# P2-sematik.net
KiCad netlist of a schematic drawn in Altium Designer
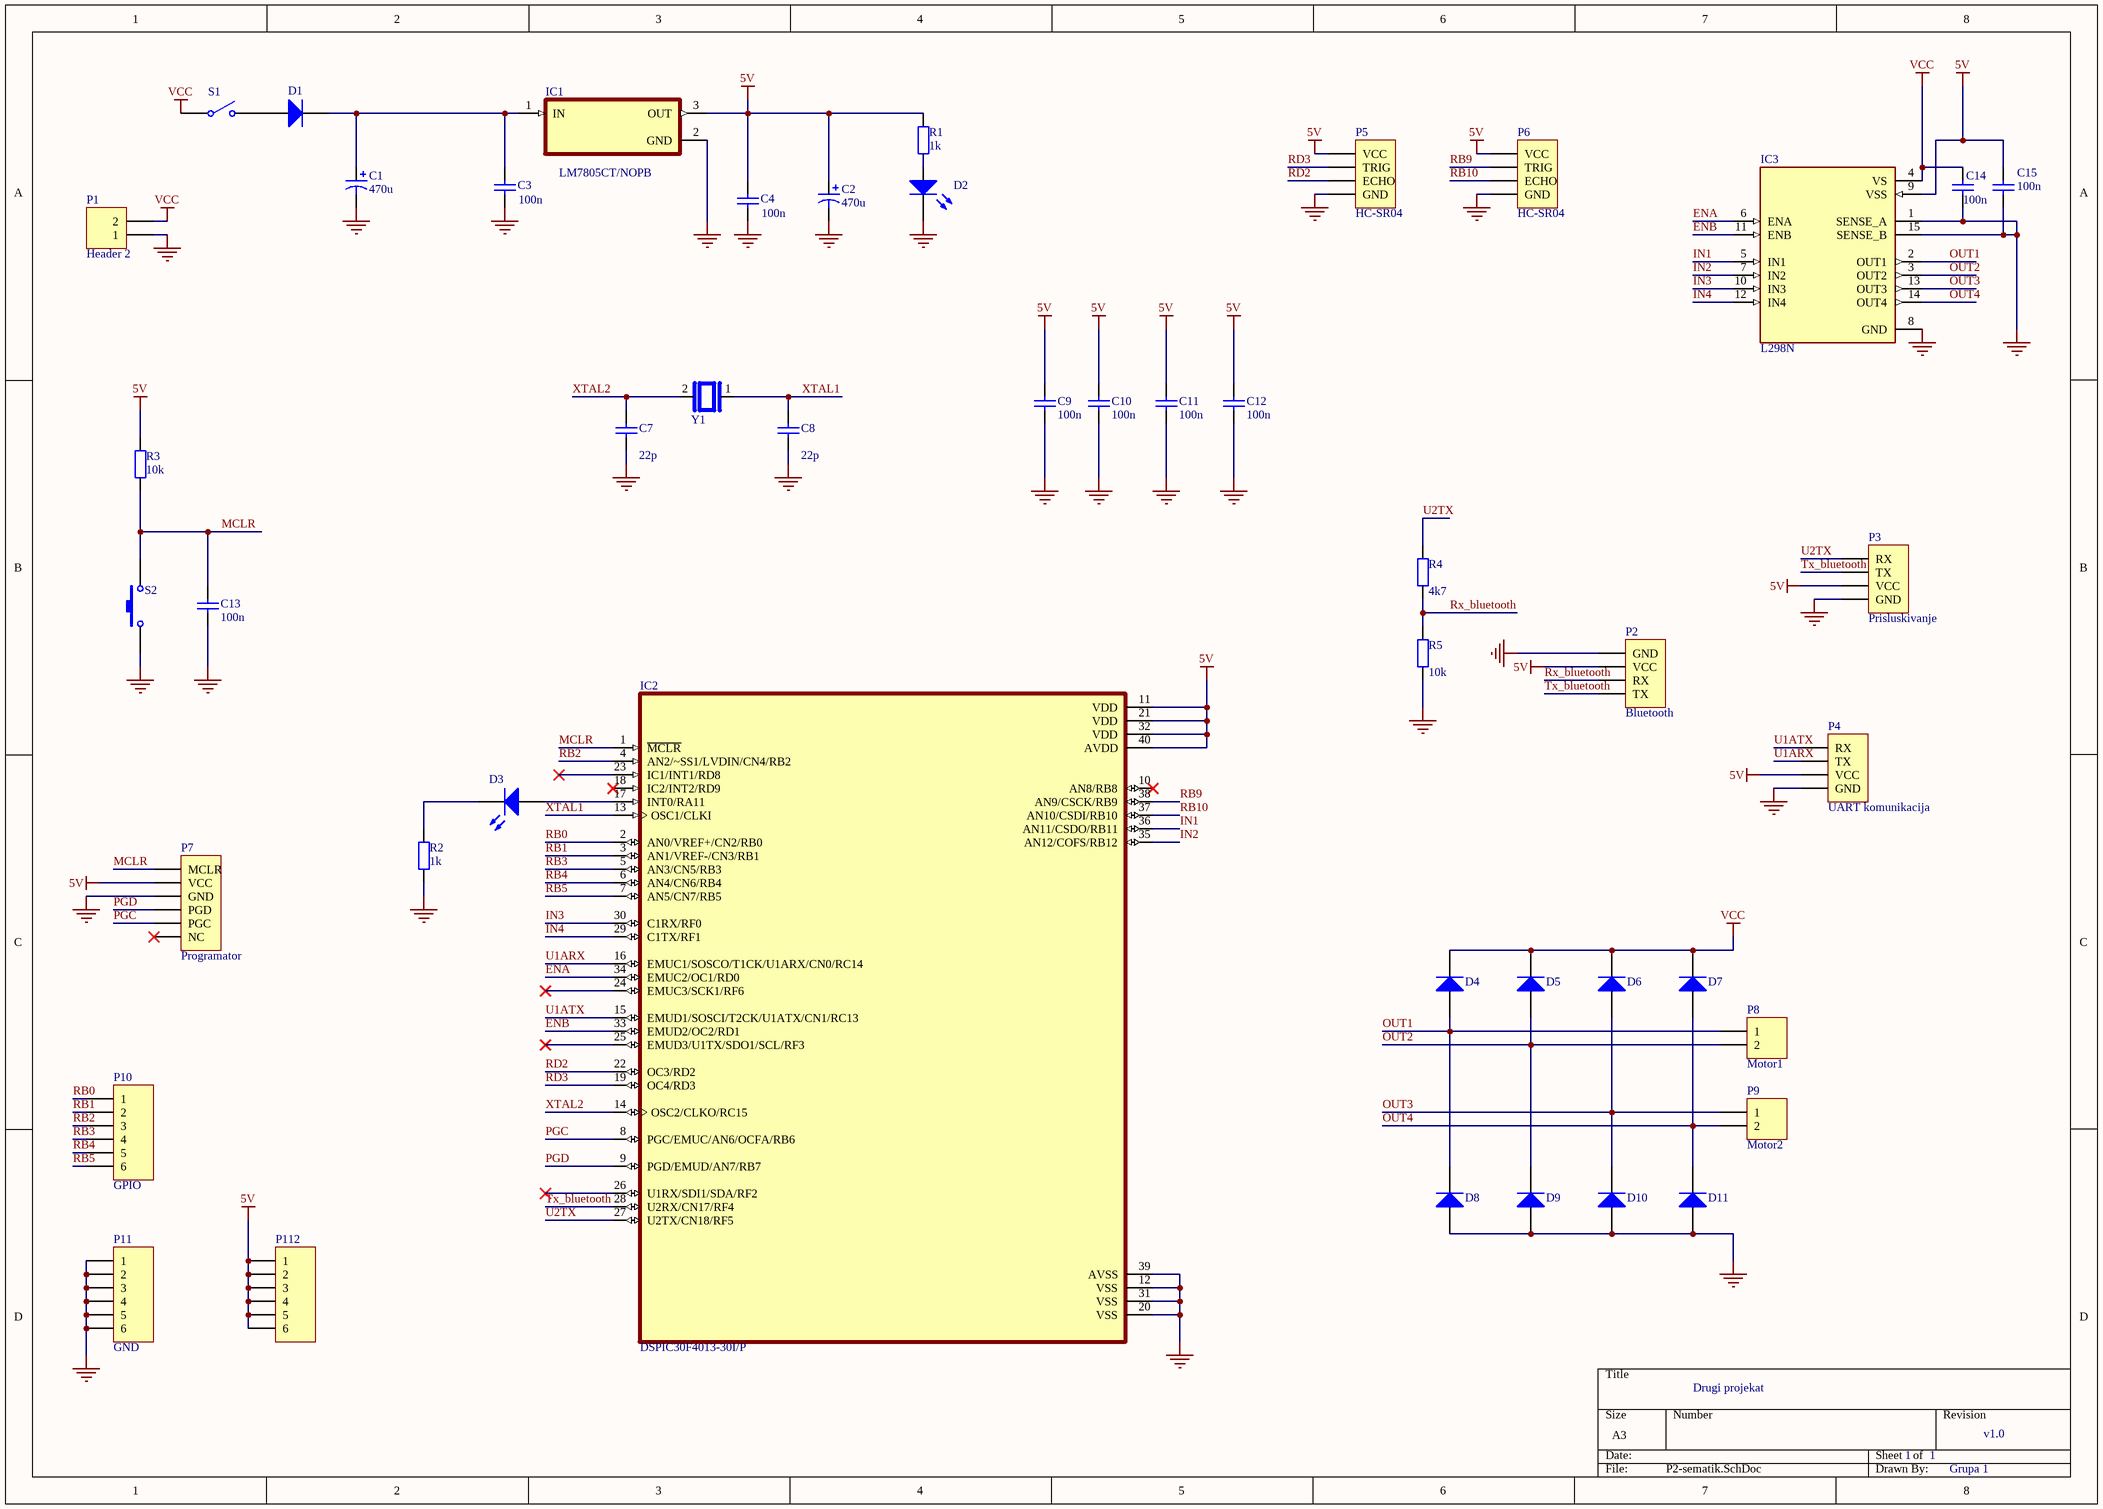
[diagram p0: P2-sematik.SchDoc]

(export (version "E")
  (design (tool "Eeschema 10.0.6"))
  (components
    (comp (ref "C1")
      (value "470u")
      (footprint "elektrolitski kondenzator")
      (description "Polarized Capacitor (Radial)")
      (fields (field (name "Comment") "Cap Pol1") (field (name "PUBLISHER") "Altium Limited"))
      (libsource (lib "Miscellaneous Devices") (part "Cap Pol1"))
    )
    (comp (ref "C2")
      (value "470u")
      (footprint "elektrolitski kondenzator")
      (description "Polarized Capacitor (Radial)")
      (fields (field (name "Comment") "Cap Pol1") (field (name "PUBLISHER") "Altium Limited"))
      (libsource (lib "Miscellaneous Devices") (part "Cap Pol1"))
    )
    (comp (ref "C3")
      (value "100n")
      (footprint "RAD-0.1")
      (description "Capacitor")
      (fields (field (name "Comment") "Cap") (field (name "PUBLISHER") "Altium Limited"))
      (libsource (lib "Miscellaneous Devices") (part "Cap"))
    )
    (comp (ref "C4")
      (value "100n")
      (footprint "RAD-0.1")
      (description "Capacitor")
      (fields (field (name "Comment") "Cap") (field (name "PUBLISHER") "Altium Limited"))
      (libsource (lib "Miscellaneous Devices") (part "Cap"))
    )
    (comp (ref "C7")
      (value "22p")
      (footprint "RAD-0.1")
      (description "Capacitor")
      (fields (field (name "Comment") "Cap") (field (name "PUBLISHER") "Altium Limited"))
      (libsource (lib "Miscellaneous Devices") (part "Cap"))
    )
    (comp (ref "C8")
      (value "22p")
      (footprint "RAD-0.1")
      (description "Capacitor")
      (fields (field (name "Comment") "Cap") (field (name "PUBLISHER") "Altium Limited"))
      (libsource (lib "Miscellaneous Devices") (part "Cap"))
    )
    (comp (ref "C9")
      (value "100n")
      (footprint "RAD-0.1")
      (description "Capacitor")
      (fields (field (name "Comment") "Cap") (field (name "PUBLISHER") "Altium Limited"))
      (libsource (lib "Miscellaneous Devices") (part "Cap"))
    )
    (comp (ref "C10")
      (value "100n")
      (footprint "RAD-0.1")
      (description "Capacitor")
      (fields (field (name "Comment") "Cap") (field (name "PUBLISHER") "Altium Limited"))
      (libsource (lib "Miscellaneous Devices") (part "Cap"))
    )
    (comp (ref "C11")
      (value "100n")
      (footprint "RAD-0.1")
      (description "Capacitor")
      (fields (field (name "Comment") "Cap") (field (name "PUBLISHER") "Altium Limited"))
      (libsource (lib "Miscellaneous Devices") (part "Cap"))
    )
    (comp (ref "C12")
      (value "100n")
      (footprint "RAD-0.1")
      (description "Capacitor")
      (fields (field (name "Comment") "Cap") (field (name "PUBLISHER") "Altium Limited"))
      (libsource (lib "Miscellaneous Devices") (part "Cap"))
    )
    (comp (ref "C13")
      (value "100n")
      (footprint "RAD-0.1")
      (description "Capacitor")
      (fields (field (name "Comment") "Cap") (field (name "PUBLISHER") "Altium Limited"))
      (libsource (lib "Miscellaneous Devices") (part "Cap"))
    )
    (comp (ref "C14")
      (value "100n")
      (footprint "RAD-0.1")
      (description "Capacitor")
      (fields (field (name "Comment") "Cap") (field (name "PUBLISHER") "Altium Limited"))
      (libsource (lib "Miscellaneous Devices") (part "Cap"))
    )
    (comp (ref "C15")
      (value "100n")
      (footprint "RAD-0.1")
      (description "Capacitor")
      (fields (field (name "Comment") "Cap") (field (name "PUBLISHER") "Altium Limited"))
      (libsource (lib "Miscellaneous Devices") (part "Cap"))
    )
    (comp (ref "D1")
      (value "Diode 1N4007")
      (footprint "DO-41")
      (description "1 Amp General Purpose Rectifier")
      (fields (field (name "PUBLISHER") "Altium Limited"))
      (libsource (lib "Miscellaneous Devices") (part "Diode 1N4007"))
    )
    (comp (ref "D2")
      (value "LED0")
      (footprint "LED dioda")
      (description "Typical INFRARED GaAs LED")
      (fields (field (name "PUBLISHER") "Altium Limited"))
      (libsource (lib "Miscellaneous Devices") (part "LED0"))
    )
    (comp (ref "D3")
      (value "LED0")
      (footprint "LED dioda")
      (description "Typical INFRARED GaAs LED")
      (fields (field (name "PUBLISHER") "Altium Limited"))
      (libsource (lib "Miscellaneous Devices") (part "LED0"))
    )
    (comp (ref "D4")
      (value "Diode 1N4007")
      (footprint "DO-41")
      (description "1 Amp General Purpose Rectifier")
      (fields (field (name "PUBLISHER") "Altium Limited"))
      (libsource (lib "Miscellaneous Devices") (part "Diode 1N4007"))
    )
    (comp (ref "D5")
      (value "Diode 1N4007")
      (footprint "DO-41")
      (description "1 Amp General Purpose Rectifier")
      (fields (field (name "PUBLISHER") "Altium Limited"))
      (libsource (lib "Miscellaneous Devices") (part "Diode 1N4007"))
    )
    (comp (ref "D6")
      (value "Diode 1N4007")
      (footprint "DO-41")
      (description "1 Amp General Purpose Rectifier")
      (fields (field (name "PUBLISHER") "Altium Limited"))
      (libsource (lib "Miscellaneous Devices") (part "Diode 1N4007"))
    )
    (comp (ref "D7")
      (value "Diode 1N4007")
      (footprint "DO-41")
      (description "1 Amp General Purpose Rectifier")
      (fields (field (name "PUBLISHER") "Altium Limited"))
      (libsource (lib "Miscellaneous Devices") (part "Diode 1N4007"))
    )
    (comp (ref "D8")
      (value "Diode 1N4007")
      (footprint "DO-41")
      (description "1 Amp General Purpose Rectifier")
      (fields (field (name "PUBLISHER") "Altium Limited"))
      (libsource (lib "Miscellaneous Devices") (part "Diode 1N4007"))
    )
    (comp (ref "D9")
      (value "Diode 1N4007")
      (footprint "DO-41")
      (description "1 Amp General Purpose Rectifier")
      (fields (field (name "PUBLISHER") "Altium Limited"))
      (libsource (lib "Miscellaneous Devices") (part "Diode 1N4007"))
    )
    (comp (ref "D10")
      (value "Diode 1N4007")
      (footprint "DO-41")
      (description "1 Amp General Purpose Rectifier")
      (fields (field (name "PUBLISHER") "Altium Limited"))
      (libsource (lib "Miscellaneous Devices") (part "Diode 1N4007"))
    )
    (comp (ref "D11")
      (value "Diode 1N4007")
      (footprint "DO-41")
      (description "1 Amp General Purpose Rectifier")
      (fields (field (name "PUBLISHER") "Altium Limited"))
      (libsource (lib "Miscellaneous Devices") (part "Diode 1N4007"))
    )
    (comp (ref "IC1")
      (value "LM7805CT/NOPB")
      (footprint "TO254P1054X470X1955-3")
      (fields (field (name "MF") "{'manufacturer': u'Texas Instruments'}"))
      (libsource (lib "LM7805CT_NOPB") (part "LM7805CT/NOPB"))
    )
    (comp (ref "IC2")
      (value "DSPIC30F4013-30I/P")
      (footprint "Mikrokontroler")
      (description "Digital Signal Processors, DSP, DSC General Purpose ¦ Microchip Technology Inc. DSPIC30F4013-30I/P")
      (fields (field (name "MF") "Microchip"))
      (libsource (lib "DSPIC30F4013-30I_P") (part "DSPIC30F4013-30I/P"))
    )
    (comp (ref "IC3")
      (value "L298N")
      (footprint "TO127P2020X500X2100-15")
      (description "Dual Full Bridge Motor Driver 15-Pin(15+Tab) MULTIWATT V Tube")
      (libsource (lib "L298N") (part "L298N"))
    )
    (comp (ref "P1")
      (value "Header 2")
      (footprint "HDR1X2")
      (description "Header, 2-Pin")
      (fields (field (name "PUBLISHER") "Altium Limited"))
      (libsource (lib "") (part "Header 2_1"))
    )
    (comp (ref "P2")
      (value "Bluetooth")
      (footprint "HDR1X4")
      (description "Header, 4-Pin")
      (fields (field (name "PUBLISHER") "Altium Limited"))
      (libsource (lib "Miscellaneous Connectors") (part "Header 4"))
    )
    (comp (ref "P3")
      (value "Prisluskivanje")
      (footprint "HDR1X4")
      (description "Header, 4-Pin")
      (fields (field (name "PUBLISHER") "Altium Limited"))
      (libsource (lib "Miscellaneous Connectors") (part "Header 4"))
    )
    (comp (ref "P4")
      (value "UART komunikacija")
      (footprint "HDR1X4")
      (description "Header, 4-Pin")
      (fields (field (name "PUBLISHER") "Altium Limited"))
      (libsource (lib "Miscellaneous Connectors") (part "Header 4"))
    )
    (comp (ref "P5")
      (value "HC-SR04")
      (footprint "HDR1X4")
      (description "Header, 4-Pin")
      (fields (field (name "PUBLISHER") "Altium Limited"))
      (libsource (lib "Miscellaneous Connectors") (part "Header 4"))
    )
    (comp (ref "P6")
      (value "HC-SR04")
      (footprint "HDR1X4")
      (description "Header, 4-Pin")
      (fields (field (name "PUBLISHER") "Altium Limited"))
      (libsource (lib "Miscellaneous Connectors") (part "Header 4"))
    )
    (comp (ref "P7")
      (value "Programator")
      (footprint "HDR1X6")
      (description "Header, 6-Pin")
      (fields (field (name "PUBLISHER") "Altium Limited"))
      (libsource (lib "Miscellaneous Connectors") (part "Header 6"))
    )
    (comp (ref "P8")
      (value "Motor1")
      (footprint "HDR1X2")
      (description "Header, 2-Pin")
      (fields (field (name "PUBLISHER") "Altium Limited"))
      (libsource (lib "Miscellaneous Connectors") (part "Header 2"))
    )
    (comp (ref "P9")
      (value "Motor2")
      (footprint "HDR1X2")
      (description "Header, 2-Pin")
      (fields (field (name "PUBLISHER") "Altium Limited"))
      (libsource (lib "Miscellaneous Connectors") (part "Header 2"))
    )
    (comp (ref "P10")
      (value "GPIO")
      (footprint "HDR1X6")
      (description "Header, 6-Pin")
      (fields (field (name "PUBLISHER") "Altium Limited"))
      (libsource (lib "Miscellaneous Connectors") (part "Header 6"))
    )
    (comp (ref "P11")
      (value "GND")
      (footprint "HDR1X6")
      (description "Header, 6-Pin")
      (fields (field (name "PUBLISHER") "Altium Limited"))
      (libsource (lib "Miscellaneous Connectors") (part "Header 6"))
    )
    (comp (ref "P112")
      (value "Header 6")
      (footprint "HDR1X6")
      (description "Header, 6-Pin")
      (fields (field (name "PUBLISHER") "Altium Limited"))
      (libsource (lib "Miscellaneous Connectors") (part "Header 6"))
    )
    (comp (ref "R1")
      (value "1k")
      (footprint "AXIAL-0.3")
      (description "Resistor")
      (fields (field (name "Comment") "Res2") (field (name "PUBLISHER") "Altium Limited"))
      (libsource (lib "Miscellaneous Devices") (part "Res2"))
    )
    (comp (ref "R2")
      (value "1k")
      (footprint "AXIAL-0.3")
      (description "Resistor")
      (fields (field (name "Comment") "Res2") (field (name "PUBLISHER") "Altium Limited"))
      (libsource (lib "") (part "Res2_1"))
    )
    (comp (ref "R3")
      (value "10k")
      (footprint "AXIAL-0.3")
      (description "Resistor")
      (fields (field (name "Comment") "Res2") (field (name "PUBLISHER") "Altium Limited"))
      (libsource (lib "Miscellaneous Devices") (part "Res2"))
    )
    (comp (ref "R4")
      (value "4k7")
      (footprint "AXIAL-0.3")
      (description "Resistor")
      (fields (field (name "Comment") "Res2") (field (name "PUBLISHER") "Altium Limited"))
      (libsource (lib "Miscellaneous Devices") (part "Res2"))
    )
    (comp (ref "R5")
      (value "10k")
      (footprint "AXIAL-0.3")
      (description "Resistor")
      (fields (field (name "Comment") "Res2") (field (name "PUBLISHER") "Altium Limited"))
      (libsource (lib "Miscellaneous Devices") (part "Res2"))
    )
    (comp (ref "S1")
      (value "SW-SPST")
      (footprint "SPST-2")
      (description "Single-Pole, Single-Throw Switch")
      (fields (field (name "PUBLISHER") "Altium Limited"))
      (libsource (lib "Miscellaneous Devices") (part "SW-SPST"))
    )
    (comp (ref "S2")
      (value "SW-PB")
      (footprint "SPST-2")
      (description "Switch")
      (fields (field (name "PUBLISHER") "Altium Limited"))
      (libsource (lib "Miscellaneous Devices") (part "SW-PB"))
    )
    (comp (ref "Y1")
      (value "HC-49/U-S16000000ABJB")
      (footprint "XTAL_HC49P488W43L1150T466H350")
      (description "16 MHz Â±30ppm Crystal 18pF 50 Ohms HC-49/US")
      (fields (field (name "MF") "Citizen Finedevice"))
      (libsource (lib "HC-49_U-S16000000ABJB") (part "HC-49/U-S16000000ABJB"))
    )
  )
  (nets
    (net (code "1") (name "/ENA") (class "Default")
      (node (ref "IC2") (pin "34") (pinfunction "EMUC2/OC1/RD0_34") (pintype "bidirectional"))
      (node (ref "IC3") (pin "6") (pinfunction "ENA_6") (pintype "input"))
    )
    (net (code "2") (name "/ENB") (class "Default")
      (node (ref "IC2") (pin "33") (pinfunction "EMUD2/OC2/RD1_33") (pintype "bidirectional"))
      (node (ref "IC3") (pin "11") (pinfunction "ENB_11") (pintype "input"))
    )
    (net (code "3") (name "/IN1") (class "Default")
      (node (ref "IC2") (pin "36") (pinfunction "AN11/CSDO/RB11_36") (pintype "bidirectional"))
      (node (ref "IC3") (pin "5") (pinfunction "IN1_5") (pintype "input"))
    )
    (net (code "4") (name "/IN2") (class "Default")
      (node (ref "IC2") (pin "35") (pinfunction "AN12/COFS/RB12_35") (pintype "bidirectional"))
      (node (ref "IC3") (pin "7") (pinfunction "IN2_7") (pintype "input"))
    )
    (net (code "5") (name "/IN3") (class "Default")
      (node (ref "IC2") (pin "30") (pinfunction "C1RX/RF0_30") (pintype "bidirectional"))
      (node (ref "IC3") (pin "10") (pinfunction "IN3_10") (pintype "input"))
    )
    (net (code "6") (name "/IN4") (class "Default")
      (node (ref "IC2") (pin "29") (pinfunction "C1TX/RF1_29") (pintype "bidirectional"))
      (node (ref "IC3") (pin "12") (pinfunction "IN4_12") (pintype "input"))
    )
    (net (code "7") (name "/MCLR") (class "Default")
      (node (ref "C13") (pin "2") (pinfunction "2_2") (pintype "passive"))
      (node (ref "IC2") (pin "1") (pinfunction "~{MCLR}_1") (pintype "input"))
      (node (ref "P7") (pin "1") (pinfunction "MCLR_1") (pintype "passive"))
      (node (ref "R3") (pin "1") (pinfunction "1_1") (pintype "passive"))
      (node (ref "S2") (pin "2") (pinfunction "2_2") (pintype "passive"))
    )
    (net (code "8") (name "/OUT1") (class "Default")
      (node (ref "D4") (pin "1") (pinfunction "A_1") (pintype "passive"))
      (node (ref "D8") (pin "2") (pinfunction "K_2") (pintype "passive"))
      (node (ref "IC3") (pin "2") (pinfunction "OUT1_2") (pintype "output"))
      (node (ref "P8") (pin "1") (pinfunction "1_1") (pintype "passive"))
    )
    (net (code "9") (name "/OUT2") (class "Default")
      (node (ref "D5") (pin "1") (pinfunction "A_1") (pintype "passive"))
      (node (ref "D9") (pin "2") (pinfunction "K_2") (pintype "passive"))
      (node (ref "IC3") (pin "3") (pinfunction "OUT2_3") (pintype "output"))
      (node (ref "P8") (pin "2") (pinfunction "2_2") (pintype "passive"))
    )
    (net (code "10") (name "/OUT3") (class "Default")
      (node (ref "D10") (pin "2") (pinfunction "K_2") (pintype "passive"))
      (node (ref "D6") (pin "1") (pinfunction "A_1") (pintype "passive"))
      (node (ref "IC3") (pin "13") (pinfunction "OUT3_13") (pintype "output"))
      (node (ref "P9") (pin "1") (pinfunction "1_1") (pintype "passive"))
    )
    (net (code "11") (name "/OUT4") (class "Default")
      (node (ref "D11") (pin "2") (pinfunction "K_2") (pintype "passive"))
      (node (ref "D7") (pin "1") (pinfunction "A_1") (pintype "passive"))
      (node (ref "IC3") (pin "14") (pinfunction "OUT4_14") (pintype "output"))
      (node (ref "P9") (pin "2") (pinfunction "2_2") (pintype "passive"))
    )
    (net (code "12") (name "/PGC") (class "Default")
      (node (ref "IC2") (pin "8") (pinfunction "PGC/EMUC/AN6/OCFA/RB6_8") (pintype "bidirectional"))
      (node (ref "P7") (pin "5") (pinfunction "PGC_5") (pintype "passive"))
    )
    (net (code "13") (name "/PGD") (class "Default")
      (node (ref "IC2") (pin "9") (pinfunction "PGD/EMUD/AN7/RB7_9") (pintype "bidirectional"))
      (node (ref "P7") (pin "4") (pinfunction "PGD_4") (pintype "passive"))
    )
    (net (code "14") (name "/RB0") (class "Default")
      (node (ref "IC2") (pin "2") (pinfunction "AN0/VREF+/CN2/RB0_2") (pintype "bidirectional"))
      (node (ref "P10") (pin "1") (pinfunction "MCLR_1") (pintype "passive"))
    )
    (net (code "15") (name "/RB1") (class "Default")
      (node (ref "IC2") (pin "3") (pinfunction "AN1/VREF-/CN3/RB1_3") (pintype "bidirectional"))
      (node (ref "P10") (pin "2") (pinfunction "VCC_2") (pintype "passive"))
    )
    (net (code "16") (name "/RB2") (class "Default")
      (node (ref "IC2") (pin "4") (pinfunction "AN2/~SS1/LVDIN/CN4/RB2_4") (pintype "input"))
      (node (ref "P10") (pin "3") (pinfunction "GND_3") (pintype "passive"))
    )
    (net (code "17") (name "/RB3") (class "Default")
      (node (ref "IC2") (pin "5") (pinfunction "AN3/CN5/RB3_5") (pintype "bidirectional"))
      (node (ref "P10") (pin "4") (pinfunction "PGD_4") (pintype "passive"))
    )
    (net (code "18") (name "/RB4") (class "Default")
      (node (ref "IC2") (pin "6") (pinfunction "AN4/CN6/RB4_6") (pintype "bidirectional"))
      (node (ref "P10") (pin "5") (pinfunction "PGC_5") (pintype "passive"))
    )
    (net (code "19") (name "/RB5") (class "Default")
      (node (ref "IC2") (pin "7") (pinfunction "AN5/CN7/RB5_7") (pintype "bidirectional"))
      (node (ref "P10") (pin "6") (pinfunction "NC_6") (pintype "passive"))
    )
    (net (code "20") (name "/RB9") (class "Default")
      (node (ref "IC2") (pin "38") (pinfunction "AN9/CSCK/RB9_38") (pintype "bidirectional"))
      (node (ref "P6") (pin "2") (pinfunction "TX_2") (pintype "passive"))
    )
    (net (code "21") (name "/RB10") (class "Default")
      (node (ref "IC2") (pin "37") (pinfunction "AN10/CSDI/RB10_37") (pintype "bidirectional"))
      (node (ref "P6") (pin "3") (pinfunction "VCC_3") (pintype "passive"))
    )
    (net (code "22") (name "/RD2") (class "Default")
      (node (ref "IC2") (pin "22") (pinfunction "OC3/RD2_22") (pintype "bidirectional"))
      (node (ref "P5") (pin "3") (pinfunction "VCC_3") (pintype "passive"))
    )
    (net (code "23") (name "/RD3") (class "Default")
      (node (ref "IC2") (pin "19") (pinfunction "OC4/RD3_19") (pintype "bidirectional"))
      (node (ref "P5") (pin "2") (pinfunction "TX_2") (pintype "passive"))
    )
    (net (code "24") (name "/Rx_bluetooth") (class "Default")
      (node (ref "P2") (pin "3") (pinfunction "VCC_3") (pintype "passive"))
      (node (ref "R4") (pin "1") (pinfunction "1_1") (pintype "passive"))
      (node (ref "R5") (pin "2") (pinfunction "2_2") (pintype "passive"))
    )
    (net (code "25") (name "/Tx_bluetooth") (class "Default")
      (node (ref "IC2") (pin "28") (pinfunction "U2RX/CN17/RF4_28") (pintype "bidirectional"))
      (node (ref "P2") (pin "4") (pinfunction "GND_4") (pintype "passive"))
      (node (ref "P3") (pin "2") (pinfunction "TX_2") (pintype "passive"))
    )
    (net (code "26") (name "/U1ARX") (class "Default")
      (node (ref "IC2") (pin "16") (pinfunction "EMUC1/SOSCO/T1CK/U1ARX/CN0/RC14_16") (pintype "bidirectional"))
      (node (ref "P4") (pin "2") (pinfunction "TX_2") (pintype "passive"))
    )
    (net (code "27") (name "/U1ATX") (class "Default")
      (node (ref "IC2") (pin "15") (pinfunction "EMUD1/SOSCI/T2CK/U1ATX/CN1/RC13_15") (pintype "bidirectional"))
      (node (ref "P4") (pin "1") (pinfunction "RX_1") (pintype "passive"))
    )
    (net (code "28") (name "/U2TX") (class "Default")
      (node (ref "IC2") (pin "27") (pinfunction "U2TX/CN18/RF5_27") (pintype "bidirectional"))
      (node (ref "P3") (pin "1") (pinfunction "RX_1") (pintype "passive"))
      (node (ref "R4") (pin "2") (pinfunction "2_2") (pintype "passive"))
    )
    (net (code "29") (name "/XTAL1") (class "Default")
      (node (ref "C8") (pin "2") (pinfunction "2_2") (pintype "passive"))
      (node (ref "IC2") (pin "13") (pinfunction "OSC1/CLKI_13") (pintype "input"))
      (node (ref "Y1") (pin "1") (pinfunction "1_1") (pintype "passive"))
    )
    (net (code "30") (name "/XTAL2") (class "Default")
      (node (ref "C7") (pin "2") (pinfunction "2_2") (pintype "passive"))
      (node (ref "IC2") (pin "14") (pinfunction "OSC2/CLKO/RC15_14") (pintype "bidirectional"))
      (node (ref "Y1") (pin "2") (pinfunction "2_2") (pintype "passive"))
    )
    (net (code "31") (name "5V") (class "Default")
      (node (ref "C10") (pin "1") (pinfunction "1_1") (pintype "passive"))
      (node (ref "C11") (pin "1") (pinfunction "1_1") (pintype "passive"))
      (node (ref "C12") (pin "1") (pinfunction "1_1") (pintype "passive"))
      (node (ref "C15") (pin "2") (pinfunction "2_2") (pintype "passive"))
      (node (ref "C2") (pin "1") (pinfunction "1_1") (pintype "passive"))
      (node (ref "C4") (pin "2") (pinfunction "2_2") (pintype "passive"))
      (node (ref "C9") (pin "1") (pinfunction "1_1") (pintype "passive"))
      (node (ref "IC1") (pin "3") (pinfunction "OUT_3") (pintype "output"))
      (node (ref "IC2") (pin "11") (pinfunction "VDD_11") (pintype "power_in"))
      (node (ref "IC2") (pin "21") (pinfunction "VDD_21") (pintype "power_in"))
      (node (ref "IC2") (pin "32") (pinfunction "VDD_32") (pintype "power_in"))
      (node (ref "IC2") (pin "40") (pinfunction "AVDD_40") (pintype "power_in"))
      (node (ref "IC3") (pin "9") (pinfunction "VSS_9") (pintype "input"))
      (node (ref "P112") (pin "1") (pinfunction "MCLR_1") (pintype "passive"))
      (node (ref "P112") (pin "2") (pinfunction "VCC_2") (pintype "passive"))
      (node (ref "P112") (pin "3") (pinfunction "GND_3") (pintype "passive"))
      (node (ref "P112") (pin "4") (pinfunction "PGD_4") (pintype "passive"))
      (node (ref "P112") (pin "5") (pinfunction "PGC_5") (pintype "passive"))
      (node (ref "P112") (pin "6") (pinfunction "NC_6") (pintype "passive"))
      (node (ref "P2") (pin "2") (pinfunction "TX_2") (pintype "passive"))
      (node (ref "P3") (pin "3") (pinfunction "VCC_3") (pintype "passive"))
      (node (ref "P4") (pin "3") (pinfunction "VCC_3") (pintype "passive"))
      (node (ref "P5") (pin "1") (pinfunction "RX_1") (pintype "passive"))
      (node (ref "P6") (pin "1") (pinfunction "RX_1") (pintype "passive"))
      (node (ref "P7") (pin "2") (pinfunction "VCC_2") (pintype "passive"))
      (node (ref "R1") (pin "2") (pinfunction "2_2") (pintype "passive"))
      (node (ref "R3") (pin "2") (pinfunction "2_2") (pintype "passive"))
    )
    (net (code "32") (name "GND") (class "Default")
      (node (ref "C1") (pin "2") (pinfunction "2_2") (pintype "passive"))
      (node (ref "C10") (pin "2") (pinfunction "2_2") (pintype "passive"))
      (node (ref "C11") (pin "2") (pinfunction "2_2") (pintype "passive"))
      (node (ref "C12") (pin "2") (pinfunction "2_2") (pintype "passive"))
      (node (ref "C13") (pin "1") (pinfunction "1_1") (pintype "passive"))
      (node (ref "C14") (pin "1") (pinfunction "1_1") (pintype "passive"))
      (node (ref "C15") (pin "1") (pinfunction "1_1") (pintype "passive"))
      (node (ref "C2") (pin "2") (pinfunction "2_2") (pintype "passive"))
      (node (ref "C3") (pin "1") (pinfunction "1_1") (pintype "passive"))
      (node (ref "C4") (pin "1") (pinfunction "1_1") (pintype "passive"))
      (node (ref "C7") (pin "1") (pinfunction "1_1") (pintype "passive"))
      (node (ref "C8") (pin "1") (pinfunction "1_1") (pintype "passive"))
      (node (ref "C9") (pin "2") (pinfunction "2_2") (pintype "passive"))
      (node (ref "D10") (pin "1") (pinfunction "A_1") (pintype "passive"))
      (node (ref "D11") (pin "1") (pinfunction "A_1") (pintype "passive"))
      (node (ref "D2") (pin "2") (pinfunction "K_2") (pintype "passive"))
      (node (ref "D8") (pin "1") (pinfunction "A_1") (pintype "passive"))
      (node (ref "D9") (pin "1") (pinfunction "A_1") (pintype "passive"))
      (node (ref "IC1") (pin "2") (pinfunction "GND_2") (pintype "power_in"))
      (node (ref "IC2") (pin "12") (pinfunction "VSS_12") (pintype "power_in"))
      (node (ref "IC2") (pin "20") (pinfunction "VSS_20") (pintype "power_in"))
      (node (ref "IC2") (pin "31") (pinfunction "VSS_31") (pintype "power_in"))
      (node (ref "IC2") (pin "39") (pinfunction "AVSS_39") (pintype "power_in"))
      (node (ref "IC3") (pin "1") (pinfunction "SENSE_A_1") (pintype "passive"))
      (node (ref "IC3") (pin "15") (pinfunction "SENSE_B_15") (pintype "passive"))
      (node (ref "IC3") (pin "8") (pinfunction "GND_8") (pintype "power_in"))
      (node (ref "P1") (pin "1") (pinfunction "1_1") (pintype "passive"))
      (node (ref "P11") (pin "1") (pinfunction "MCLR_1") (pintype "passive"))
      (node (ref "P11") (pin "2") (pinfunction "VCC_2") (pintype "passive"))
      (node (ref "P11") (pin "3") (pinfunction "GND_3") (pintype "passive"))
      (node (ref "P11") (pin "4") (pinfunction "PGD_4") (pintype "passive"))
      (node (ref "P11") (pin "5") (pinfunction "PGC_5") (pintype "passive"))
      (node (ref "P11") (pin "6") (pinfunction "NC_6") (pintype "passive"))
      (node (ref "P2") (pin "1") (pinfunction "RX_1") (pintype "passive"))
      (node (ref "P3") (pin "4") (pinfunction "GND_4") (pintype "passive"))
      (node (ref "P4") (pin "4") (pinfunction "GND_4") (pintype "passive"))
      (node (ref "P5") (pin "4") (pinfunction "GND_4") (pintype "passive"))
      (node (ref "P6") (pin "4") (pinfunction "GND_4") (pintype "passive"))
      (node (ref "P7") (pin "3") (pinfunction "GND_3") (pintype "passive"))
      (node (ref "R2") (pin "2") (pinfunction "2_2") (pintype "passive"))
      (node (ref "R5") (pin "1") (pinfunction "1_1") (pintype "passive"))
      (node (ref "S2") (pin "1") (pinfunction "1_1") (pintype "passive"))
    )
    (net (code "33") (name "Net-(D1-A)") (class "Default")
      (node (ref "D1") (pin "1") (pinfunction "A_1") (pintype "passive"))
      (node (ref "S1") (pin "2") (pinfunction "NO_2") (pintype "passive"))
    )
    (net (code "34") (name "Net-(D1-K)") (class "Default")
      (node (ref "C1") (pin "1") (pinfunction "1_1") (pintype "passive"))
      (node (ref "C3") (pin "2") (pinfunction "2_2") (pintype "passive"))
      (node (ref "D1") (pin "2") (pinfunction "K_2") (pintype "passive"))
      (node (ref "IC1") (pin "1") (pinfunction "IN_1") (pintype "input"))
    )
    (net (code "35") (name "Net-(D2-A)") (class "Default")
      (node (ref "D2") (pin "1") (pinfunction "A_1") (pintype "passive"))
      (node (ref "R1") (pin "1") (pinfunction "1_1") (pintype "passive"))
    )
    (net (code "36") (name "Net-(D3-A)") (class "Default")
      (node (ref "D3") (pin "1") (pinfunction "A_1") (pintype "passive"))
      (node (ref "IC2") (pin "17") (pinfunction "INT0/RA11_17") (pintype "input"))
    )
    (net (code "37") (name "Net-(D3-K)") (class "Default")
      (node (ref "D3") (pin "2") (pinfunction "K_2") (pintype "passive"))
      (node (ref "R2") (pin "1") (pinfunction "1_1") (pintype "passive"))
    )
    (net (code "38") (name "VCC") (class "Default")
      (node (ref "C14") (pin "2") (pinfunction "2_2") (pintype "passive"))
      (node (ref "D4") (pin "2") (pinfunction "K_2") (pintype "passive"))
      (node (ref "D5") (pin "2") (pinfunction "K_2") (pintype "passive"))
      (node (ref "D6") (pin "2") (pinfunction "K_2") (pintype "passive"))
      (node (ref "D7") (pin "2") (pinfunction "K_2") (pintype "passive"))
      (node (ref "IC3") (pin "4") (pinfunction "VS_4") (pintype "power_in"))
      (node (ref "P1") (pin "2") (pinfunction "2_2") (pintype "passive"))
      (node (ref "S1") (pin "1") (pinfunction "COMMON_1") (pintype "passive"))
    )
    (net (code "39") (name "unconnected-(IC2-AN8{slash}RB8-Pad10)") (class "Default")
      (node (ref "IC2") (pin "10") (pinfunction "AN8/RB8_10") (pintype "bidirectional+no_connect"))
    )
    (net (code "40") (name "unconnected-(IC2-EMUC3{slash}SCK1{slash}RF6-Pad24)") (class "Default")
      (node (ref "IC2") (pin "24") (pinfunction "EMUC3/SCK1/RF6_24") (pintype "bidirectional+no_connect"))
    )
    (net (code "41") (name "unconnected-(IC2-EMUD3{slash}U1TX{slash}SDO1{slash}SCL{slash}RF3-Pad25)") (class "Default")
      (node (ref "IC2") (pin "25") (pinfunction "EMUD3/U1TX/SDO1/SCL/RF3_25") (pintype "bidirectional+no_connect"))
    )
    (net (code "42") (name "unconnected-(IC2-IC1{slash}INT1{slash}RD8-Pad23)") (class "Default")
      (node (ref "IC2") (pin "23") (pinfunction "IC1/INT1/RD8_23") (pintype "input+no_connect"))
    )
    (net (code "43") (name "unconnected-(IC2-IC2{slash}INT2{slash}RD9-Pad18)") (class "Default")
      (node (ref "IC2") (pin "18") (pinfunction "IC2/INT2/RD9_18") (pintype "input+no_connect"))
    )
    (net (code "44") (name "unconnected-(IC2-U1RX{slash}SDI1{slash}SDA{slash}RF2-Pad26)") (class "Default")
      (node (ref "IC2") (pin "26") (pinfunction "U1RX/SDI1/SDA/RF2_26") (pintype "bidirectional+no_connect"))
    )
    (net (code "45") (name "unconnected-(P7-NC-Pad6)") (class "Default")
      (node (ref "P7") (pin "6") (pinfunction "NC_6") (pintype "passive+no_connect"))
    )
  )
)
